# Elreg_Sender_CH2.net
KiCad netlist of a schematic drawn in Altium Designer
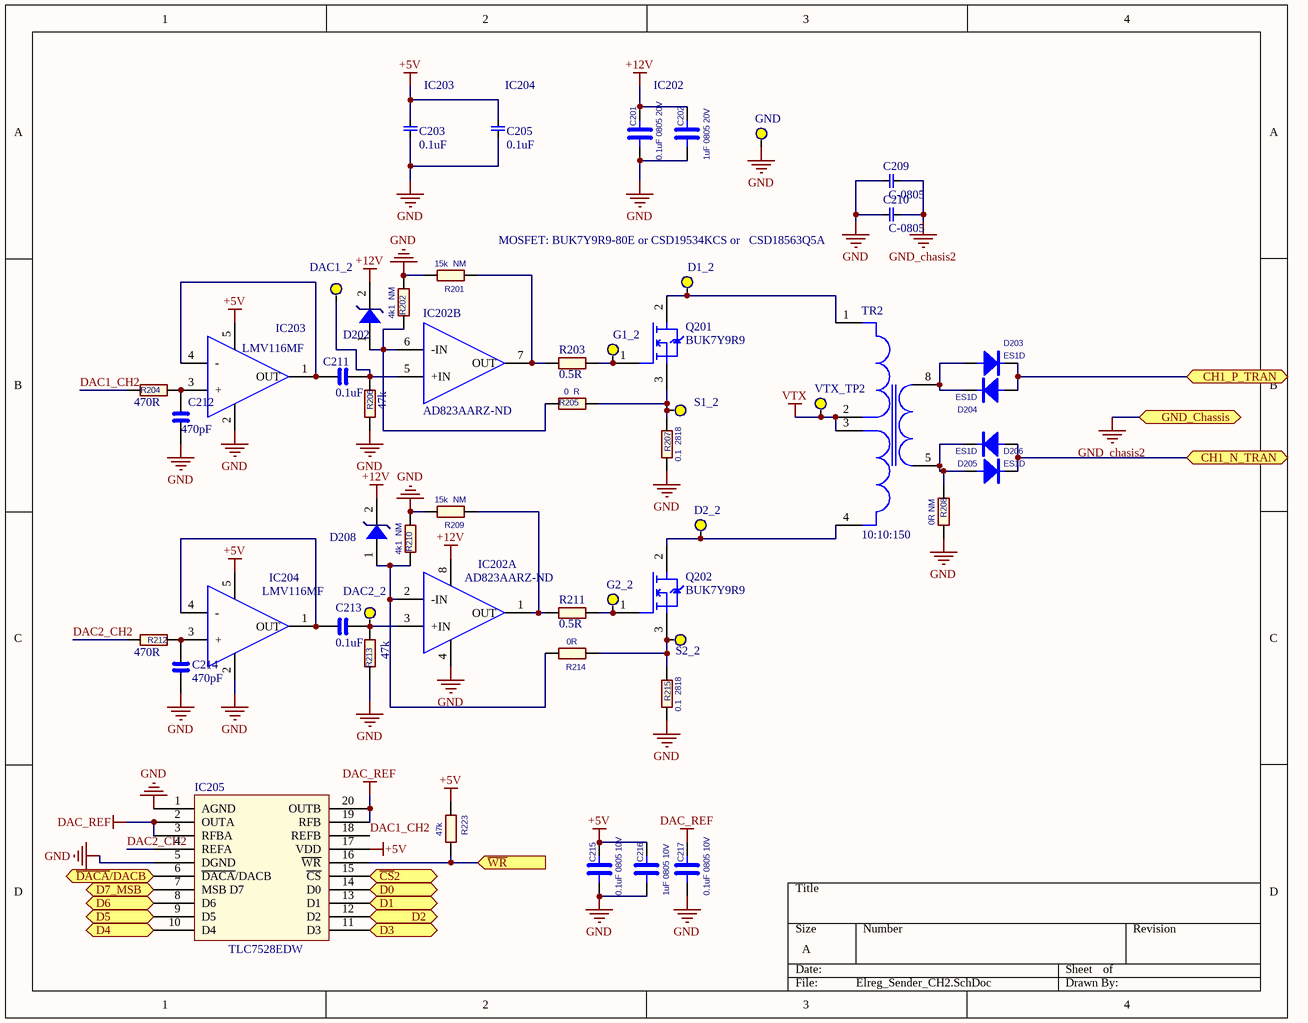
[diagram p0: Elreg_Sender_CH2.SchDoc]

(export (version "E")
  (design (tool "Eeschema 10.0.6"))
  (components
    (comp (ref "C201")
      (value "0.1uF 0805 20V")
      (footprint "C-0603")
      (description "CAP CER rrrrUF xV x% type 0805")
      (libsource (lib "Elreg (Skipper)") (part "0805CAPxxrrrrv"))
    )
    (comp (ref "C202")
      (value "1uF 0805 20V")
      (footprint "C-0603")
      (description "CAP CER rrrrUF xV x% type 0805")
      (libsource (lib "Elreg (Skipper)") (part "0805CAPxxrrrrv"))
    )
    (comp (ref "C203")
      (value "0.1uF")
      (footprint "C-0603")
      (fields (field (name "TOLERANCE") "±10%"))
      (libsource (lib "Elreg_Sender") (part "C-0805_3_3uF"))
    )
    (comp (ref "C205")
      (value "0.1uF")
      (footprint "C-0603")
      (fields (field (name "TOLERANCE") "±10%"))
      (libsource (lib "Elreg_Sender") (part "C-0805_3_3uF"))
    )
    (comp (ref "C209")
      (value "C-0805")
      (footprint "C-0805")
      (fields (field (name "TOLERANCE") "±10%"))
      (libsource (lib "Elreg_Sender") (part "C-0805"))
    )
    (comp (ref "C210")
      (value "C-0805")
      (footprint "C-0805")
      (fields (field (name "TOLERANCE") "±10%"))
      (libsource (lib "Elreg_Sender") (part "C-0805"))
    )
    (comp (ref "C211")
      (value "0.1uF")
      (footprint "C-0603")
      (description "CAP CER 0.1UF 10V X7R 0603")
      (fields (field (name "MANUFACTURER PART NUMBER") "885012206020"))
      (libsource (lib "Elreg_Sender") (part "C-0603_0_1u_10V"))
    )
    (comp (ref "C212")
      (value "470pF")
      (footprint "C-0603")
      (description "CAP CER 470p 10V C0G/NP0 0603")
      (fields (field (name "MANUFACTURER PART NUMBER") "885012006014"))
      (libsource (lib "Elreg_Sender") (part "C-0603_470p_10V"))
    )
    (comp (ref "C213")
      (value "0.1uF")
      (footprint "C-0603")
      (description "CAP CER 0.1UF 10V X7R 0603")
      (fields (field (name "MANUFACTURER PART NUMBER") "885012206020"))
      (libsource (lib "Elreg_Sender") (part "C-0603_0_1u_10V"))
    )
    (comp (ref "C214")
      (value "470pF")
      (footprint "C-0603")
      (description "CAP CER 470p 10V C0G/NP0 0603")
      (fields (field (name "MANUFACTURER PART NUMBER") "885012006014"))
      (libsource (lib "Elreg_Sender") (part "C-0603_470p_10V"))
    )
    (comp (ref "C215")
      (value "0.1uF 0805 10V")
      (footprint "C-0603")
      (description "CAP CER rrrrUF xV x% type 0805")
      (libsource (lib "Elreg (Skipper)") (part "0805CAPxxrrrrv"))
    )
    (comp (ref "C216")
      (value "1uF 0805 10V")
      (footprint "C-0603")
      (description "CAP CER rrrrUF xV x% type 0805")
      (libsource (lib "Elreg (Skipper)") (part "0805CAPxxrrrrv"))
    )
    (comp (ref "C217")
      (value "0.1uF 0805 10V")
      (footprint "C-0603")
      (description "CAP CER rrrrUF xV x% type 0805")
      (libsource (lib "Elreg (Skipper)") (part "0805CAPxxrrrrv"))
    )
    (comp (ref "D1_2")
      (value "Test_Point")
      (footprint "Test_Point")
      (libsource (lib "Elreg_Sender") (part "Test_Point"))
    )
    (comp (ref "D2_2")
      (value "Test_Point")
      (footprint "Test_Point")
      (libsource (lib "Elreg_Sender") (part "Test_Point"))
    )
    (comp (ref "D202")
      (value "Zener 12V")
      (footprint "DFN380P520X45-2N")
      (fields (field (name "BASE PART NUMBER") "CDBA140"))
      (libsource (lib "Elreg_Sender") (part "Zener 12V"))
    )
    (comp (ref "D203")
      (value "ES1D")
      (footprint "SMA")
      (description "Diode")
      (fields (field (name "MANUFACTURER") "Fairchild/ON Semiconductor"))
      (libsource (lib "Elreg_Sender") (part "ES1x"))
    )
    (comp (ref "D204")
      (value "ES1D")
      (footprint "SMA")
      (description "Diode")
      (fields (field (name "MANUFACTURER") "Fairchild/ON Semiconductor"))
      (libsource (lib "Elreg_Sender") (part "ES1x"))
    )
    (comp (ref "D205")
      (value "ES1D")
      (footprint "SMA")
      (description "Diode")
      (fields (field (name "MANUFACTURER") "Fairchild/ON Semiconductor"))
      (libsource (lib "Elreg_Sender") (part "ES1x"))
    )
    (comp (ref "D206")
      (value "ES1D")
      (footprint "SMA")
      (description "Diode")
      (fields (field (name "MANUFACTURER") "Fairchild/ON Semiconductor"))
      (libsource (lib "Elreg_Sender") (part "ES1x"))
    )
    (comp (ref "D208")
      (value "Zener 12V")
      (footprint "DFN380P520X45-2N")
      (fields (field (name "BASE PART NUMBER") "CDBA140"))
      (libsource (lib "Elreg_Sender") (part "Zener 12V"))
    )
    (comp (ref "DAC1_2")
      (value "DAC2_2")
      (footprint "Test_Point")
      (libsource (lib "Elreg_Sender") (part "Test_Point"))
    )
    (comp (ref "DAC2_2")
      (value "DAC2_2")
      (footprint "Test_Point")
      (libsource (lib "Elreg_Sender") (part "Test_Point"))
    )
    (comp (ref "G1_2")
      (value "Test_Point")
      (footprint "Test_Point")
      (libsource (lib "Elreg_Sender") (part "Test_Point"))
    )
    (comp (ref "G2_2")
      (value "Test_Point")
      (footprint "Test_Point")
      (libsource (lib "Elreg_Sender") (part "Test_Point"))
    )
    (comp (ref "IC202")
      (value "AD823AARZ-ND")
      (footprint "TSOP65P280X110-8N")
      (description "IC OPAMP JFET 16MHZ RRO 8-MSOP")
      (libsource (lib "Elreg_Sender") (part "AD823AARZ-ND"))
    )
    (comp (ref "IC203")
      (value "LMV116MF")
      (footprint "SOT-23-5")
      (libsource (lib "Elreg_Sender") (part "LMV116MF"))
    )
    (comp (ref "IC204")
      (value "LMV116MF")
      (footprint "SOT-23-5")
      (libsource (lib "Elreg_Sender") (part "LMV116MF"))
    )
    (comp (ref "IC205")
      (value "TLC7528EDW")
      (footprint "SOIC-20")
      (libsource (lib "Elreg_Sender") (part "TLC7528EDW"))
    )
    (comp (ref "Q201")
      (value "BUK7Y9R9")
      (footprint "BUK7Y9R)")
      (libsource (lib "Elreg_Sender") (part "BUK7Y9R9"))
    )
    (comp (ref "Q202")
      (value "BUK7Y9R9")
      (footprint "BUK7Y9R)")
      (libsource (lib "Elreg_Sender") (part "BUK7Y9R9"))
    )
    (comp (ref "R201")
      (value "15k  NM")
      (footprint "R-0603")
      (description "RES xx OHM 1/8W 5% 0805 SMD")
      (libsource (lib "Elreg (Skipper)") (part "CRCW0805xxxxJN Default"))
    )
    (comp (ref "R202")
      (value "4k1  NM")
      (footprint "R-0603")
      (description "RES xx OHM 1/8W 5% 0805 SMD")
      (libsource (lib "") (part "CRCW0805xxxxJN Default_1"))
    )
    (comp (ref "R203") (value "0.5R") (footprint "R-0603") (libsource (lib "Elreg_Sender") (part "RES-0805")))
    (comp (ref "R204")
      (value "470R")
      (footprint "R-0603")
      (description "RES SMD 470 OHM 1% 0.4W 0805")
      (fields (field (name "TOLERANCE") "±5%") (field (name "MANUFACTURER PART NUMBER") "ESR10EZPF1001"))
      (libsource (lib "Elreg_Sender") (part "R-0603_470R"))
    )
    (comp (ref "R205")
      (value "0  R")
      (footprint "R-0603")
      (description "RES xx OHM 1/8W 5% 0805 SMD")
      (libsource (lib "Elreg (Skipper)") (part "CRCW0805xxxxJN Default"))
    )
    (comp (ref "R206")
      (value "47k")
      (footprint "R-0603")
      (description "RES SMD 47k 1% 0.4W 0805")
      (fields (field (name "TOLERANCE") "±5%") (field (name "MANUFACTURER PART NUMBER") "ESR10EZPF1001"))
      (libsource (lib "Elreg_Sender") (part "R-0603_47k"))
    )
    (comp (ref "R207")
      (value "0.1  2818")
      (footprint "RES2818")
      (description "0.1Ohm 10W")
      (libsource (lib "") (part "CRCW0805xxxxJN Default_2"))
    )
    (comp (ref "R208")
      (value "0R NM")
      (footprint "RES-0805")
      (description "RES xx OHM 1/8W 5% 0805 SMD")
      (libsource (lib "") (part "CRCW0805xxxxJN Default_1"))
    )
    (comp (ref "R209")
      (value "15k  NM")
      (footprint "R-0603")
      (description "RES xx OHM 1/8W 5% 0805 SMD")
      (libsource (lib "Elreg (Skipper)") (part "CRCW0805xxxxJN Default"))
    )
    (comp (ref "R210")
      (value "4k1  NM")
      (footprint "R-0603")
      (description "RES xx OHM 1/8W 5% 0805 SMD")
      (libsource (lib "") (part "CRCW0805xxxxJN Default_1"))
    )
    (comp (ref "R211") (value "0.5R") (footprint "R-0603") (libsource (lib "Elreg_Sender") (part "RES-0805")))
    (comp (ref "R212")
      (value "470R")
      (footprint "R-0603")
      (description "RES SMD 470 OHM 1% 0.4W 0805")
      (fields (field (name "TOLERANCE") "±5%") (field (name "MANUFACTURER PART NUMBER") "ESR10EZPF1001"))
      (libsource (lib "Elreg_Sender") (part "R-0603_470R"))
    )
    (comp (ref "R213")
      (value "47k")
      (footprint "R-0603")
      (description "RES SMD 47k 1% 0.4W 0805")
      (fields (field (name "TOLERANCE") "±5%") (field (name "MANUFACTURER PART NUMBER") "ESR10EZPF1001"))
      (libsource (lib "") (part "R-0603_47k_1"))
    )
    (comp (ref "R214")
      (value "0R")
      (footprint "R-0603")
      (description "RES xx OHM 1/8W 5% 0805 SMD")
      (libsource (lib "Elreg (Skipper)") (part "CRCW0805xxxxJN Default"))
    )
    (comp (ref "R215")
      (value "0.1  2818")
      (footprint "RES2818")
      (description "0.1Ohm 10W")
      (libsource (lib "") (part "CRCW0805xxxxJN Default_2"))
    )
    (comp (ref "R223")
      (value "47k")
      (footprint "R-0603")
      (description "RES xx OHM 1/8W 5% 0805 SMD")
      (libsource (lib "") (part "CRCW0805xxxxJN Default_1"))
    )
    (comp (ref "S1_2")
      (value "Test_Point")
      (footprint "Test_Point")
      (libsource (lib "Elreg_Sender") (part "Test_Point"))
    )
    (comp (ref "S2_2")
      (value "Test_Point")
      (footprint "Test_Point")
      (libsource (lib "Elreg_Sender") (part "Test_Point"))
    )
    (comp (ref "TP6")
      (value "GND")
      (footprint "Test_Point")
      (libsource (lib "Elreg_Sender") (part "Test_Point"))
    )
    (comp (ref "TR2")
      (value "10:10:150")
      (footprint "Trafo_15x15")
      (libsource (lib "Elreg_Sender") (part "TRAFO_15x15"))
    )
    (comp (ref "VTX_TP2")
      (value "Test_Point")
      (footprint "Test_Point")
      (libsource (lib "Elreg_Sender") (part "Test_Point"))
    )
  )
  (nets
    (net (code "1") (name "+5V") (class "Default")
      (node (ref "C203") (pin "2") (pinfunction "G_2") (pintype "passive"))
      (node (ref "C205") (pin "2") (pinfunction "G_2") (pintype "passive"))
      (node (ref "C215") (pin "2") (pinfunction "2_2") (pintype "passive"))
      (node (ref "C216") (pin "2") (pinfunction "2_2") (pintype "passive"))
      (node (ref "IC203") (pin "5") (pinfunction "+Vs_5") (pintype "passive"))
      (node (ref "IC204") (pin "5") (pinfunction "+Vs_5") (pintype "passive"))
      (node (ref "IC205") (pin "17") (pinfunction "VDD_17") (pintype "passive"))
      (node (ref "R223") (pin "2") (pinfunction "2_2") (pintype "passive"))
    )
    (net (code "2") (name "+12V") (class "Default")
      (node (ref "C201") (pin "2") (pinfunction "2_2") (pintype "passive"))
      (node (ref "C202") (pin "2") (pinfunction "2_2") (pintype "passive"))
      (node (ref "D202") (pin "2") (pinfunction "A_2") (pintype "passive"))
      (node (ref "D208") (pin "2") (pinfunction "A_2") (pintype "passive"))
      (node (ref "IC202") (pin "8") (pinfunction "+Vs_8") (pintype "passive"))
    )
    (net (code "3") (name "/CH1_N_TRAN") (class "Default")
      (node (ref "D205") (pin "1") (pinfunction "A_1") (pintype "passive"))
      (node (ref "D206") (pin "2") (pinfunction "C_2") (pintype "passive"))
    )
    (net (code "4") (name "/CH1_P_TRAN") (class "Default")
      (node (ref "D203") (pin "2") (pinfunction "C_2") (pintype "passive"))
      (node (ref "D204") (pin "1") (pinfunction "A_1") (pintype "passive"))
    )
    (net (code "5") (name "/D0") (class "Default")
      (node (ref "IC205") (pin "14") (pinfunction "D0_14") (pintype "passive"))
    )
    (net (code "6") (name "/D1") (class "Default")
      (node (ref "IC205") (pin "13") (pinfunction "D1_13") (pintype "passive"))
    )
    (net (code "7") (name "/D2") (class "Default")
      (node (ref "IC205") (pin "12") (pinfunction "D2_12") (pintype "passive"))
    )
    (net (code "8") (name "/D3") (class "Default")
      (node (ref "IC205") (pin "11") (pinfunction "D3_11") (pintype "passive"))
    )
    (net (code "9") (name "/D4") (class "Default")
      (node (ref "IC205") (pin "10") (pinfunction "D4_10") (pintype "passive"))
    )
    (net (code "10") (name "/D5") (class "Default")
      (node (ref "IC205") (pin "9") (pinfunction "D5_9") (pintype "passive"))
    )
    (net (code "11") (name "/D6") (class "Default")
      (node (ref "IC205") (pin "8") (pinfunction "D6_8") (pintype "passive"))
    )
    (net (code "12") (name "/D7_MSB") (class "Default")
      (node (ref "IC205") (pin "7") (pinfunction "MSB_D7_7") (pintype "passive"))
    )
    (net (code "13") (name "/DAC1_CH2") (class "Default")
      (node (ref "IC205") (pin "18") (pinfunction "REFB_18") (pintype "passive"))
      (node (ref "R204") (pin "1") (pinfunction "1_1") (pintype "passive"))
    )
    (net (code "14") (name "/DAC2_CH2") (class "Default")
      (node (ref "IC205") (pin "4") (pinfunction "REFA_4") (pintype "passive"))
      (node (ref "R212") (pin "1") (pinfunction "1_1") (pintype "passive"))
    )
    (net (code "15") (name "/~{CS}2") (class "Default")
      (node (ref "IC205") (pin "15") (pinfunction "~{CS}_15") (pintype "passive"))
    )
    (net (code "16") (name "/~{DACA}{slash}DACB") (class "Default")
      (node (ref "IC205") (pin "6") (pinfunction "~{DACA}/DACB_6") (pintype "passive"))
    )
    (net (code "17") (name "/~{WR}") (class "Default")
      (node (ref "IC205") (pin "16") (pinfunction "~{WR}_16") (pintype "passive"))
      (node (ref "R223") (pin "1") (pinfunction "1_1") (pintype "passive"))
    )
    (net (code "18") (name "DAC_REF") (class "Default")
      (node (ref "C217") (pin "2") (pinfunction "2_2") (pintype "passive"))
      (node (ref "IC205") (pin "19") (pinfunction "RFB_19") (pintype "passive"))
      (node (ref "IC205") (pin "2") (pinfunction "OUTA_2") (pintype "passive"))
      (node (ref "IC205") (pin "20") (pinfunction "OUTB_20") (pintype "passive"))
      (node (ref "IC205") (pin "3") (pinfunction "RFBA_3") (pintype "passive"))
    )
    (net (code "19") (name "GND") (class "Default")
      (node (ref "C201") (pin "1") (pinfunction "1_1") (pintype "passive"))
      (node (ref "C202") (pin "1") (pinfunction "1_1") (pintype "passive"))
      (node (ref "C203") (pin "1") (pinfunction "G_1") (pintype "passive"))
      (node (ref "C205") (pin "1") (pinfunction "G_1") (pintype "passive"))
      (node (ref "C209") (pin "1") (pinfunction "G_1") (pintype "passive"))
      (node (ref "C210") (pin "1") (pinfunction "G_1") (pintype "passive"))
      (node (ref "C212") (pin "2") (pintype "passive"))
      (node (ref "C214") (pin "1") (pintype "passive"))
      (node (ref "C215") (pin "1") (pinfunction "1_1") (pintype "passive"))
      (node (ref "C216") (pin "1") (pinfunction "1_1") (pintype "passive"))
      (node (ref "C217") (pin "1") (pinfunction "1_1") (pintype "passive"))
      (node (ref "IC202") (pin "4") (pinfunction "-Vs_4") (pintype "passive"))
      (node (ref "IC203") (pin "2") (pinfunction "-Vs_2") (pintype "passive"))
      (node (ref "IC204") (pin "2") (pinfunction "-Vs_2") (pintype "passive"))
      (node (ref "IC205") (pin "1") (pinfunction "AGND_1") (pintype "passive"))
      (node (ref "IC205") (pin "5") (pinfunction "DGND_5") (pintype "passive"))
      (node (ref "R201") (pin "1") (pinfunction "1_1") (pintype "passive"))
      (node (ref "R202") (pin "2") (pinfunction "2_2") (pintype "passive"))
      (node (ref "R206") (pin "1") (pinfunction "1_1") (pintype "passive"))
      (node (ref "R207") (pin "2") (pinfunction "2_2") (pintype "passive"))
      (node (ref "R208") (pin "1") (pinfunction "1_1") (pintype "passive"))
      (node (ref "R209") (pin "1") (pinfunction "1_1") (pintype "passive"))
      (node (ref "R210") (pin "2") (pinfunction "2_2") (pintype "passive"))
      (node (ref "R213") (pin "2") (pinfunction "2_2") (pintype "passive"))
      (node (ref "R215") (pin "2") (pinfunction "2_2") (pintype "passive"))
      (node (ref "TP6") (pin "1") (pinfunction "1_1") (pintype "passive"))
    )
    (net (code "20") (name "GND_chasis2") (class "Default")
      (node (ref "C209") (pin "2") (pinfunction "G_2") (pintype "passive"))
      (node (ref "C210") (pin "2") (pinfunction "G_2") (pintype "passive"))
    )
    (net (code "21") (name "Net-(D1_2-Pad1)") (class "Default")
      (node (ref "D1_2") (pin "1") (pinfunction "1_1") (pintype "passive"))
      (node (ref "Q201") (pin "2") (pinfunction "G_2") (pintype "passive"))
      (node (ref "TR2") (pin "1") (pinfunction "G_1") (pintype "passive"))
    )
    (net (code "22") (name "Net-(D2_2-Pad1)") (class "Default")
      (node (ref "D2_2") (pin "1") (pinfunction "1_1") (pintype "passive"))
      (node (ref "Q202") (pin "2") (pinfunction "G_2") (pintype "passive"))
      (node (ref "TR2") (pin "4") (pinfunction "G_4") (pintype "passive"))
    )
    (net (code "23") (name "Net-(D203-A)") (class "Default")
      (node (ref "D203") (pin "1") (pinfunction "A_1") (pintype "passive"))
      (node (ref "D204") (pin "2") (pinfunction "C_2") (pintype "passive"))
      (node (ref "TR2") (pin "8") (pinfunction "G_8") (pintype "passive"))
    )
    (net (code "24") (name "Net-(D205-C)") (class "Default")
      (node (ref "D205") (pin "2") (pinfunction "C_2") (pintype "passive"))
      (node (ref "D206") (pin "1") (pinfunction "A_1") (pintype "passive"))
      (node (ref "R208") (pin "2") (pinfunction "2_2") (pintype "passive"))
      (node (ref "TR2") (pin "5") (pinfunction "G_5") (pintype "passive"))
    )
    (net (code "25") (name "Net-(G1_2-Pad1)") (class "Default")
      (node (ref "G1_2") (pin "1") (pinfunction "1_1") (pintype "passive"))
      (node (ref "Q201") (pin "1") (pinfunction "G_1") (pintype "passive"))
      (node (ref "R203") (pin "2") (pinfunction "2_2") (pintype "passive"))
    )
    (net (code "26") (name "Net-(G2_2-Pad1)") (class "Default")
      (node (ref "G2_2") (pin "1") (pinfunction "1_1") (pintype "passive"))
      (node (ref "Q202") (pin "1") (pinfunction "G_1") (pintype "passive"))
      (node (ref "R211") (pin "2") (pinfunction "2_2") (pintype "passive"))
    )
    (net (code "27") (name "Net-(IC202A-+IN)") (class "Default")
      (node (ref "C213") (pin "1") (pintype "passive"))
      (node (ref "DAC2_2") (pin "1") (pinfunction "1_1") (pintype "passive"))
      (node (ref "IC202") (pin "3") (pinfunction "+IN_3") (pintype "passive"))
      (node (ref "R213") (pin "1") (pinfunction "1_1") (pintype "passive"))
    )
    (net (code "28") (name "Net-(IC202A--IN)") (class "Default")
      (node (ref "D208") (pin "1") (pinfunction "A_1") (pintype "passive"))
      (node (ref "IC202") (pin "2") (pinfunction "-IN_2") (pintype "passive"))
      (node (ref "R210") (pin "1") (pinfunction "1_1") (pintype "passive"))
      (node (ref "R214") (pin "1") (pinfunction "1_1") (pintype "passive"))
    )
    (net (code "29") (name "Net-(IC202A-OUT)") (class "Default")
      (node (ref "IC202") (pin "1") (pinfunction "OUT_1") (pintype "passive"))
      (node (ref "R209") (pin "2") (pinfunction "2_2") (pintype "passive"))
      (node (ref "R211") (pin "1") (pinfunction "1_1") (pintype "passive"))
    )
    (net (code "30") (name "Net-(IC202B-+IN)") (class "Default")
      (node (ref "C211") (pin "1") (pintype "passive"))
      (node (ref "DAC1_2") (pin "1") (pinfunction "1_1") (pintype "passive"))
      (node (ref "IC202") (pin "5") (pinfunction "+IN_5") (pintype "passive"))
      (node (ref "R206") (pin "2") (pinfunction "2_2") (pintype "passive"))
    )
    (net (code "31") (name "Net-(IC202B--IN)") (class "Default")
      (node (ref "D202") (pin "1") (pinfunction "A_1") (pintype "passive"))
      (node (ref "IC202") (pin "6") (pinfunction "-IN_6") (pintype "passive"))
      (node (ref "R202") (pin "1") (pinfunction "1_1") (pintype "passive"))
      (node (ref "R205") (pin "1") (pinfunction "1_1") (pintype "passive"))
    )
    (net (code "32") (name "Net-(IC202B-OUT)") (class "Default")
      (node (ref "IC202") (pin "7") (pinfunction "OUT_7") (pintype "passive"))
      (node (ref "R201") (pin "2") (pinfunction "2_2") (pintype "passive"))
      (node (ref "R203") (pin "1") (pinfunction "1_1") (pintype "passive"))
    )
    (net (code "33") (name "Net-(IC203-+)") (class "Default")
      (node (ref "C212") (pin "1") (pintype "passive"))
      (node (ref "IC203") (pin "3") (pinfunction "+_3") (pintype "passive"))
      (node (ref "R204") (pin "2") (pinfunction "2_2") (pintype "passive"))
    )
    (net (code "34") (name "Net-(IC203--)") (class "Default")
      (node (ref "C211") (pin "2") (pintype "passive"))
      (node (ref "IC203") (pin "1") (pinfunction "OUT_1") (pintype "passive"))
      (node (ref "IC203") (pin "4") (pinfunction "-_4") (pintype "passive"))
    )
    (net (code "35") (name "Net-(IC204-+)") (class "Default")
      (node (ref "C214") (pin "2") (pintype "passive"))
      (node (ref "IC204") (pin "3") (pinfunction "+_3") (pintype "passive"))
      (node (ref "R212") (pin "2") (pinfunction "2_2") (pintype "passive"))
    )
    (net (code "36") (name "Net-(IC204--)") (class "Default")
      (node (ref "C213") (pin "2") (pintype "passive"))
      (node (ref "IC204") (pin "1") (pinfunction "OUT_1") (pintype "passive"))
      (node (ref "IC204") (pin "4") (pinfunction "-_4") (pintype "passive"))
    )
    (net (code "37") (name "Net-(Q201-G-Pad3)") (class "Default")
      (node (ref "Q201") (pin "3") (pinfunction "G_3") (pintype "passive"))
      (node (ref "R205") (pin "2") (pinfunction "2_2") (pintype "passive"))
      (node (ref "R207") (pin "1") (pinfunction "1_1") (pintype "passive"))
      (node (ref "S1_2") (pin "1") (pinfunction "1_1") (pintype "passive"))
    )
    (net (code "38") (name "Net-(Q202-G-Pad3)") (class "Default")
      (node (ref "Q202") (pin "3") (pinfunction "G_3") (pintype "passive"))
      (node (ref "R214") (pin "2") (pinfunction "2_2") (pintype "passive"))
      (node (ref "R215") (pin "1") (pinfunction "1_1") (pintype "passive"))
      (node (ref "S2_2") (pin "1") (pinfunction "1_1") (pintype "passive"))
    )
    (net (code "39") (name "VTX") (class "Default")
      (node (ref "TR2") (pin "2") (pinfunction "G_2") (pintype "passive"))
      (node (ref "TR2") (pin "3") (pinfunction "G_3") (pintype "passive"))
      (node (ref "VTX_TP2") (pin "1") (pinfunction "1_1") (pintype "passive"))
    )
  )
)
